# Main.net
KiCad netlist of a schematic drawn in Altium Designer
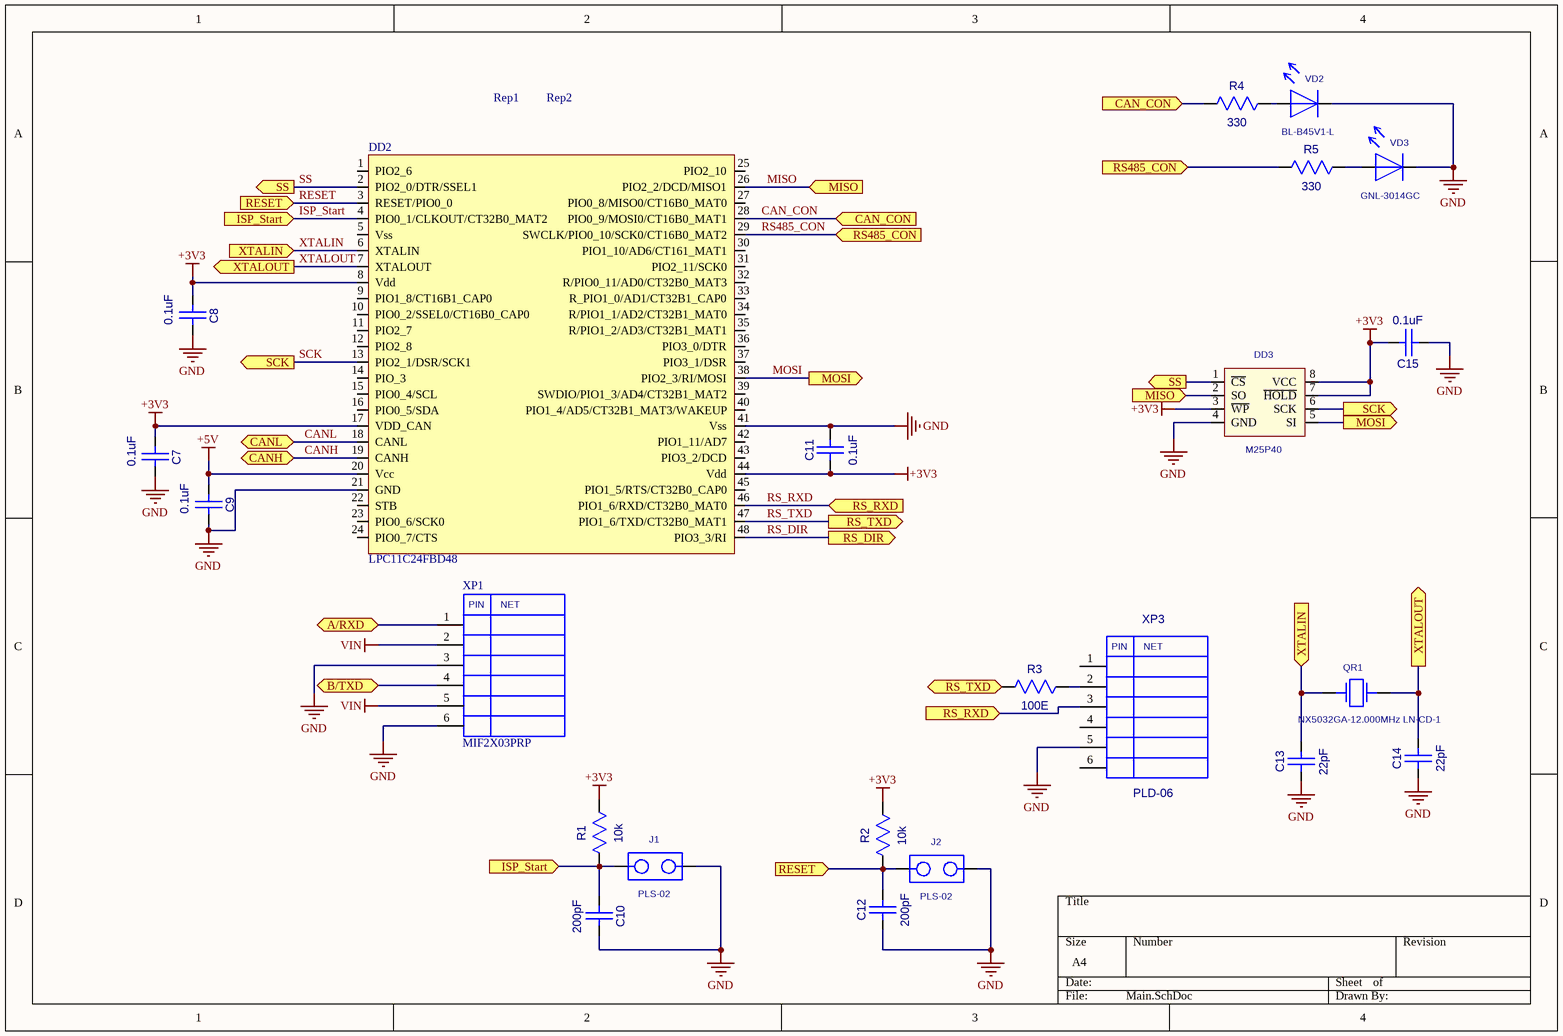
[diagram p0: Main.SchDoc]

(export (version "E")
  (design (tool "Eeschema 10.0.6"))
  (components
    (comp (ref "C7")
      (value "0.1uF")
      (footprint "CC0603-3M")
      (description "CC0603")
      (libsource (lib "gprs_modem") (part "CC0603"))
    )
    (comp (ref "C8")
      (value "0.1uF")
      (footprint "CC0603-3M")
      (description "CC0603")
      (libsource (lib "gprs_modem") (part "CC0603"))
    )
    (comp (ref "C9")
      (value "0.1uF")
      (footprint "CC0603-3M")
      (description "CC0603")
      (libsource (lib "gprs_modem") (part "CC0603"))
    )
    (comp (ref "C10")
      (value "200pF")
      (footprint "CC0603-3M")
      (description "CC0603")
      (libsource (lib "gprs_modem") (part "CC0603"))
    )
    (comp (ref "C11")
      (value "0.1uF")
      (footprint "CC0603")
      (description "CC0603")
      (libsource (lib "gprs_modem") (part "CC0603"))
    )
    (comp (ref "C12")
      (value "200pF")
      (footprint "CC0603-3M")
      (description "CC0603")
      (libsource (lib "gprs_modem") (part "CC0603"))
    )
    (comp (ref "C13")
      (value "22pF")
      (footprint "CC0603-3M")
      (description "CC0603")
      (libsource (lib "gprs_modem") (part "CC0603"))
    )
    (comp (ref "C14")
      (value "22pF")
      (footprint "CC0603-3M")
      (description "CC0603")
      (libsource (lib "gprs_modem") (part "CC0603"))
    )
    (comp (ref "C15")
      (value "0.1uF")
      (footprint "CC0603-3M")
      (description "CC0603")
      (libsource (lib "gprs_modem2") (part "CC0603"))
    )
    (comp (ref "DD2")
      (value "LPC11C24FBD48")
      (footprint "LQFP48")
      (libsource (lib "VHF") (part "LPC11C24FBD48"))
    )
    (comp (ref "DD3")
      (value "M25P40")
      (footprint "EIAJ_SO8")
      (description "S25FL016A0LMFI01")
      (libsource (lib "gprs_modem") (part "S25FL016A0LMFI01"))
    )
    (comp (ref "J1") (value "PLS-02") (footprint "PLS-02") (libsource (lib "gprs_modem") (part "PLS-02")))
    (comp (ref "J2") (value "PLS-02") (footprint "PLS-02") (libsource (lib "gprs_modem") (part "PLS-02")))
    (comp (ref "QR1")
      (value "NX5032GA-12.000MHz LN-CD-1")
      (footprint "AC5032_2")
      (description "AC5032/2")
      (libsource (lib "gprs_modem") (part "AC5032_2"))
    )
    (comp (ref "R1")
      (value "10k")
      (footprint "RC0603-3M")
      (description "RC0603")
      (libsource (lib "gprs_modem") (part "RC0603"))
    )
    (comp (ref "R2")
      (value "10k")
      (footprint "RC0603-3M")
      (description "RC0603")
      (libsource (lib "gprs_modem") (part "RC0603"))
    )
    (comp (ref "R3")
      (value "100E")
      (footprint "RC0603-3M")
      (description "RC0603")
      (libsource (lib "gprs_modem") (part "RC0603"))
    )
    (comp (ref "R4")
      (value "330")
      (footprint "RC0603-3M")
      (description "RC0603")
      (libsource (lib "gprs_modem") (part "RC0603"))
    )
    (comp (ref "R5")
      (value "330")
      (footprint "RC0603-3M")
      (description "RC0603")
      (libsource (lib "gprs_modem") (part "RC0603"))
    )
    (comp (ref "Rep1")
      (value "REPER1.2")
      (footprint "REPER1.2")
      (libsource (lib "gprs_modem") (part "REPER1.2"))
    )
    (comp (ref "Rep2")
      (value "REPER1.2")
      (footprint "REPER1.2")
      (libsource (lib "gprs_modem") (part "REPER1.2"))
    )
    (comp (ref "VD2")
      (value "BL-B45V1-L")
      (footprint "LED3")
      (description "LED_3")
      (libsource (lib "gprs_modem") (part "LED_3"))
    )
    (comp (ref "VD3")
      (value "GNL-3014GC")
      (footprint "LED3")
      (description "LED_3")
      (libsource (lib "gprs_modem") (part "LED_3"))
    )
    (comp (ref "XP1")
      (value "MIF2X03PRP")
      (footprint "MIF2X03PRP")
      (description "MIF2x03PRP")
      (libsource (lib "gprs_modem") (part "MIF2X03PRP"))
    )
    (comp (ref "XP3")
      (value "PLD-06")
      (footprint "PIN6")
      (description "PLD06")
      (libsource (lib "gprs_modem") (part "PLD-06"))
    )
  )
  (nets
    (net (code "1") (name "+3V3") (class "Default")
      (node (ref "C11") (pin "1") (pinfunction "A_1") (pintype "passive"))
      (node (ref "C15") (pin "2") (pinfunction "B_2") (pintype "passive"))
      (node (ref "C7") (pin "1") (pinfunction "A_1") (pintype "passive"))
      (node (ref "C8") (pin "1") (pinfunction "A_1") (pintype "passive"))
      (node (ref "DD2") (pin "17") (pinfunction "VDD_CAN_17") (pintype "passive"))
      (node (ref "DD2") (pin "44") (pinfunction "Vdd_44") (pintype "passive"))
      (node (ref "DD2") (pin "8") (pinfunction "Vdd_8") (pintype "passive"))
      (node (ref "DD3") (pin "3") (pinfunction "~{WP}_3") (pintype "passive"))
      (node (ref "DD3") (pin "7") (pinfunction "~{HOLD}_7") (pintype "passive"))
      (node (ref "DD3") (pin "8") (pinfunction "VCC_8") (pintype "passive"))
      (node (ref "R1") (pin "2") (pinfunction "B_2") (pintype "passive"))
      (node (ref "R2") (pin "2") (pinfunction "B_2") (pintype "passive"))
    )
    (net (code "2") (name "+5V") (class "Default")
      (node (ref "C9") (pin "1") (pinfunction "A_1") (pintype "passive"))
      (node (ref "DD2") (pin "20") (pinfunction "Vcc_20") (pintype "passive"))
    )
    (net (code "3") (name "/A{slash}RXD") (class "Default")
      (node (ref "XP1") (pin "1") (pinfunction "1_1") (pintype "passive"))
    )
    (net (code "4") (name "/B{slash}TXD") (class "Default")
      (node (ref "XP1") (pin "4") (pinfunction "4_4") (pintype "passive"))
    )
    (net (code "5") (name "/CANH") (class "Default")
      (node (ref "DD2") (pin "19") (pinfunction "CANH_19") (pintype "passive"))
    )
    (net (code "6") (name "/CANL") (class "Default")
      (node (ref "DD2") (pin "18") (pinfunction "CANL_18") (pintype "passive"))
    )
    (net (code "7") (name "/CAN_CON") (class "Default")
      (node (ref "DD2") (pin "28") (pinfunction "PIO0_9/MOSI0/CT16B0_MAT1_28") (pintype "passive"))
      (node (ref "R4") (pin "1") (pinfunction "A_1") (pintype "passive"))
    )
    (net (code "8") (name "/ISP_Start") (class "Default")
      (node (ref "C10") (pin "1") (pinfunction "A_1") (pintype "passive"))
      (node (ref "DD2") (pin "4") (pinfunction "PIO0_1/CLKOUT/CT32B0_MAT2_4") (pintype "passive"))
      (node (ref "J1") (pin "1") (pintype "passive"))
      (node (ref "R1") (pin "1") (pinfunction "A_1") (pintype "passive"))
    )
    (net (code "9") (name "/MISO") (class "Default")
      (node (ref "DD2") (pin "26") (pinfunction "PIO2_2/DCD/MISO1_26") (pintype "passive"))
      (node (ref "DD3") (pin "2") (pinfunction "SO_2") (pintype "passive"))
    )
    (net (code "10") (name "/MOSI") (class "Default")
      (node (ref "DD2") (pin "38") (pinfunction "PIO2_3/RI/MOSI_38") (pintype "passive"))
      (node (ref "DD3") (pin "5") (pinfunction "SI_5") (pintype "passive"))
    )
    (net (code "11") (name "/RESET") (class "Default")
      (node (ref "C12") (pin "2") (pinfunction "B_2") (pintype "passive"))
      (node (ref "DD2") (pin "3") (pinfunction "RESET/PIO0_0_3") (pintype "passive"))
      (node (ref "J2") (pin "1") (pintype "passive"))
      (node (ref "R2") (pin "1") (pinfunction "A_1") (pintype "passive"))
    )
    (net (code "12") (name "/RS485_CON") (class "Default")
      (node (ref "DD2") (pin "29") (pinfunction "SWCLK/PIO0_10/SCK0/CT16B0_MAT2_29") (pintype "passive"))
      (node (ref "R5") (pin "1") (pinfunction "A_1") (pintype "passive"))
    )
    (net (code "13") (name "/RS_DIR") (class "Default")
      (node (ref "DD2") (pin "48") (pinfunction "PIO3_3/RI_48") (pintype "passive"))
    )
    (net (code "14") (name "/RS_RXD") (class "Default")
      (node (ref "DD2") (pin "46") (pinfunction "PIO1_6/RXD/CT32B0_MAT0_46") (pintype "passive"))
      (node (ref "XP3") (pin "3") (pinfunction "3_3") (pintype "passive"))
    )
    (net (code "15") (name "/RS_TXD") (class "Default")
      (node (ref "DD2") (pin "47") (pinfunction "PIO1_6/TXD/CT32B0_MAT1_47") (pintype "passive"))
      (node (ref "R3") (pin "1") (pinfunction "A_1") (pintype "passive"))
    )
    (net (code "16") (name "/SCK") (class "Default")
      (node (ref "DD2") (pin "13") (pinfunction "PIO2_1/DSR/SCK1_13") (pintype "passive"))
      (node (ref "DD3") (pin "6") (pinfunction "SCK_6") (pintype "passive"))
    )
    (net (code "17") (name "/SS") (class "Default")
      (node (ref "DD2") (pin "2") (pinfunction "PIO2_0/DTR/SSEL1_2") (pintype "passive"))
      (node (ref "DD3") (pin "1") (pinfunction "~{CS}_1") (pintype "passive"))
    )
    (net (code "18") (name "/XTALIN") (class "Default")
      (node (ref "C13") (pin "2") (pinfunction "B_2") (pintype "passive"))
      (node (ref "DD2") (pin "6") (pinfunction "XTALIN_6") (pintype "passive"))
      (node (ref "QR1") (pin "1") (pintype "passive"))
    )
    (net (code "19") (name "/XTALOUT") (class "Default")
      (node (ref "C14") (pin "2") (pinfunction "B_2") (pintype "passive"))
      (node (ref "DD2") (pin "7") (pinfunction "XTALOUT_7") (pintype "passive"))
      (node (ref "QR1") (pin "2") (pintype "passive"))
    )
    (net (code "20") (name "GND") (class "Default")
      (node (ref "C10") (pin "2") (pinfunction "B_2") (pintype "passive"))
      (node (ref "C11") (pin "2") (pinfunction "B_2") (pintype "passive"))
      (node (ref "C12") (pin "1") (pinfunction "A_1") (pintype "passive"))
      (node (ref "C13") (pin "1") (pinfunction "A_1") (pintype "passive"))
      (node (ref "C14") (pin "1") (pinfunction "A_1") (pintype "passive"))
      (node (ref "C15") (pin "1") (pinfunction "A_1") (pintype "passive"))
      (node (ref "C7") (pin "2") (pinfunction "B_2") (pintype "passive"))
      (node (ref "C8") (pin "2") (pinfunction "B_2") (pintype "passive"))
      (node (ref "C9") (pin "2") (pinfunction "B_2") (pintype "passive"))
      (node (ref "DD2") (pin "21") (pinfunction "GND_21") (pintype "passive"))
      (node (ref "DD2") (pin "41") (pinfunction "Vss_41") (pintype "passive"))
      (node (ref "DD3") (pin "4") (pinfunction "GND_4") (pintype "passive"))
      (node (ref "J1") (pin "2") (pintype "passive"))
      (node (ref "J2") (pin "2") (pintype "passive"))
      (node (ref "VD2") (pin "1") (pintype "passive"))
      (node (ref "VD3") (pin "1") (pintype "passive"))
      (node (ref "XP1") (pin "3") (pinfunction "3_3") (pintype "passive"))
      (node (ref "XP1") (pin "6") (pinfunction "6_6") (pintype "passive"))
      (node (ref "XP3") (pin "5") (pinfunction "5_5") (pintype "passive"))
    )
    (net (code "21") (name "Net-(R3-B)") (class "Default")
      (node (ref "R3") (pin "2") (pinfunction "B_2") (pintype "passive"))
      (node (ref "XP3") (pin "2") (pinfunction "2_2") (pintype "passive"))
    )
    (net (code "22") (name "Net-(R4-B)") (class "Default")
      (node (ref "R4") (pin "2") (pinfunction "B_2") (pintype "passive"))
      (node (ref "VD2") (pin "2") (pintype "passive"))
    )
    (net (code "23") (name "Net-(R5-B)") (class "Default")
      (node (ref "R5") (pin "2") (pinfunction "B_2") (pintype "passive"))
      (node (ref "VD3") (pin "2") (pintype "passive"))
    )
    (net (code "24") (name "VIN") (class "Default")
      (node (ref "XP1") (pin "2") (pinfunction "2_2") (pintype "passive"))
      (node (ref "XP1") (pin "5") (pinfunction "5_5") (pintype "passive"))
    )
    (net (code "25") (name "unconnected-(DD2-PIO0_2{slash}SSEL0{slash}CT16B0_CAP0-Pad10)") (class "Default")
      (node (ref "DD2") (pin "10") (pinfunction "PIO0_2/SSEL0/CT16B0_CAP0_10") (pintype "passive"))
    )
    (net (code "26") (name "unconnected-(DD2-PIO0_4{slash}SCL-Pad15)") (class "Default")
      (node (ref "DD2") (pin "15") (pinfunction "PIO0_4/SCL_15") (pintype "passive"))
    )
    (net (code "27") (name "unconnected-(DD2-PIO0_5{slash}SDA-Pad16)") (class "Default")
      (node (ref "DD2") (pin "16") (pinfunction "PIO0_5/SDA_16") (pintype "passive"))
    )
    (net (code "28") (name "unconnected-(DD2-PIO0_6{slash}SCK0-Pad23)") (class "Default")
      (node (ref "DD2") (pin "23") (pinfunction "PIO0_6/SCK0_23") (pintype "passive"))
    )
    (net (code "29") (name "unconnected-(DD2-PIO0_7{slash}CTS-Pad24)") (class "Default")
      (node (ref "DD2") (pin "24") (pinfunction "PIO0_7/CTS_24") (pintype "passive"))
    )
    (net (code "30") (name "unconnected-(DD2-PIO0_8{slash}MISO0{slash}CT16B0_MAT0-Pad27)") (class "Default")
      (node (ref "DD2") (pin "27") (pinfunction "PIO0_8/MISO0/CT16B0_MAT0_27") (pintype "passive"))
    )
    (net (code "31") (name "unconnected-(DD2-PIO1_4{slash}AD5{slash}CT32B1_MAT3{slash}WAKEUP-Pad40)") (class "Default")
      (node (ref "DD2") (pin "40") (pinfunction "PIO1_4/AD5/CT32B1_MAT3/WAKEUP_40") (pintype "passive"))
    )
    (net (code "32") (name "unconnected-(DD2-PIO1_5{slash}RTS{slash}CT32B0_CAP0-Pad45)") (class "Default")
      (node (ref "DD2") (pin "45") (pinfunction "PIO1_5/RTS/CT32B0_CAP0_45") (pintype "passive"))
    )
    (net (code "33") (name "unconnected-(DD2-PIO1_8{slash}CT16B1_CAP0-Pad9)") (class "Default")
      (node (ref "DD2") (pin "9") (pinfunction "PIO1_8/CT16B1_CAP0_9") (pintype "passive"))
    )
    (net (code "34") (name "unconnected-(DD2-PIO1_10{slash}AD6{slash}CT161_MAT1-Pad30)") (class "Default")
      (node (ref "DD2") (pin "30") (pinfunction "PIO1_10/AD6/CT161_MAT1_30") (pintype "passive"))
    )
    (net (code "35") (name "unconnected-(DD2-PIO1_11{slash}AD7-Pad42)") (class "Default")
      (node (ref "DD2") (pin "42") (pinfunction "PIO1_11/AD7_42") (pintype "passive"))
    )
    (net (code "36") (name "unconnected-(DD2-PIO2_6-Pad1)") (class "Default")
      (node (ref "DD2") (pin "1") (pinfunction "PIO2_6_1") (pintype "passive"))
    )
    (net (code "37") (name "unconnected-(DD2-PIO2_7-Pad11)") (class "Default")
      (node (ref "DD2") (pin "11") (pinfunction "PIO2_7_11") (pintype "passive"))
    )
    (net (code "38") (name "unconnected-(DD2-PIO2_8-Pad12)") (class "Default")
      (node (ref "DD2") (pin "12") (pinfunction "PIO2_8_12") (pintype "passive"))
    )
    (net (code "39") (name "unconnected-(DD2-PIO2_10-Pad25)") (class "Default")
      (node (ref "DD2") (pin "25") (pinfunction "PIO2_10_25") (pintype "passive"))
    )
    (net (code "40") (name "unconnected-(DD2-PIO2_11{slash}SCK0-Pad31)") (class "Default")
      (node (ref "DD2") (pin "31") (pinfunction "PIO2_11/SCK0_31") (pintype "passive"))
    )
    (net (code "41") (name "unconnected-(DD2-PIO3_0{slash}DTR-Pad36)") (class "Default")
      (node (ref "DD2") (pin "36") (pinfunction "PIO3_0/DTR_36") (pintype "passive"))
    )
    (net (code "42") (name "unconnected-(DD2-PIO3_1{slash}DSR-Pad37)") (class "Default")
      (node (ref "DD2") (pin "37") (pinfunction "PIO3_1/DSR_37") (pintype "passive"))
    )
    (net (code "43") (name "unconnected-(DD2-PIO3_2{slash}DCD-Pad43)") (class "Default")
      (node (ref "DD2") (pin "43") (pinfunction "PIO3_2/DCD_43") (pintype "passive"))
    )
    (net (code "44") (name "unconnected-(DD2-PIO_3-Pad14)") (class "Default")
      (node (ref "DD2") (pin "14") (pinfunction "PIO_3_14") (pintype "passive"))
    )
    (net (code "45") (name "unconnected-(DD2-R_PIO1_0{slash}AD1{slash}CT32B1_CAP0-Pad33)") (class "Default")
      (node (ref "DD2") (pin "33") (pinfunction "R_PIO1_0/AD1/CT32B1_CAP0_33") (pintype "passive"))
    )
    (net (code "46") (name "unconnected-(DD2-R{slash}PIO0_11{slash}AD0{slash}CT32B0_MAT3-Pad32)") (class "Default")
      (node (ref "DD2") (pin "32") (pinfunction "R/PIO0_11/AD0/CT32B0_MAT3_32") (pintype "passive"))
    )
    (net (code "47") (name "unconnected-(DD2-R{slash}PIO1_1{slash}AD2{slash}CT32B1_MAT0-Pad34)") (class "Default")
      (node (ref "DD2") (pin "34") (pinfunction "R/PIO1_1/AD2/CT32B1_MAT0_34") (pintype "passive"))
    )
    (net (code "48") (name "unconnected-(DD2-R{slash}PIO1_2{slash}AD3{slash}CT32B1_MAT1-Pad35)") (class "Default")
      (node (ref "DD2") (pin "35") (pinfunction "R/PIO1_2/AD3/CT32B1_MAT1_35") (pintype "passive"))
    )
    (net (code "49") (name "unconnected-(DD2-STB-Pad22)") (class "Default")
      (node (ref "DD2") (pin "22") (pinfunction "STB_22") (pintype "passive"))
    )
    (net (code "50") (name "unconnected-(DD2-SWDIO{slash}PIO1_3{slash}AD4{slash}CT32B1_MAT2-Pad39)") (class "Default")
      (node (ref "DD2") (pin "39") (pinfunction "SWDIO/PIO1_3/AD4/CT32B1_MAT2_39") (pintype "passive"))
    )
    (net (code "51") (name "unconnected-(DD2-Vss-Pad5)") (class "Default")
      (node (ref "DD2") (pin "5") (pinfunction "Vss_5") (pintype "passive"))
    )
    (net (code "52") (name "unconnected-(Rep1-Pad1)") (class "Default")
      (node (ref "Rep1") (pin "1") (pintype "passive"))
    )
    (net (code "53") (name "unconnected-(Rep2-Pad1)") (class "Default")
      (node (ref "Rep2") (pin "1") (pintype "passive"))
    )
    (net (code "54") (name "unconnected-(XP3-Pad1)") (class "Default")
      (node (ref "XP3") (pin "1") (pinfunction "1_1") (pintype "passive"))
    )
    (net (code "55") (name "unconnected-(XP3-Pad4)") (class "Default")
      (node (ref "XP3") (pin "4") (pinfunction "4_4") (pintype "passive"))
    )
    (net (code "56") (name "unconnected-(XP3-Pad6)") (class "Default")
      (node (ref "XP3") (pin "6") (pinfunction "6_6") (pintype "passive"))
    )
  )
)
